# Quad_ESC_adapter.net
KiCad netlist of a schematic drawn in EAGLE
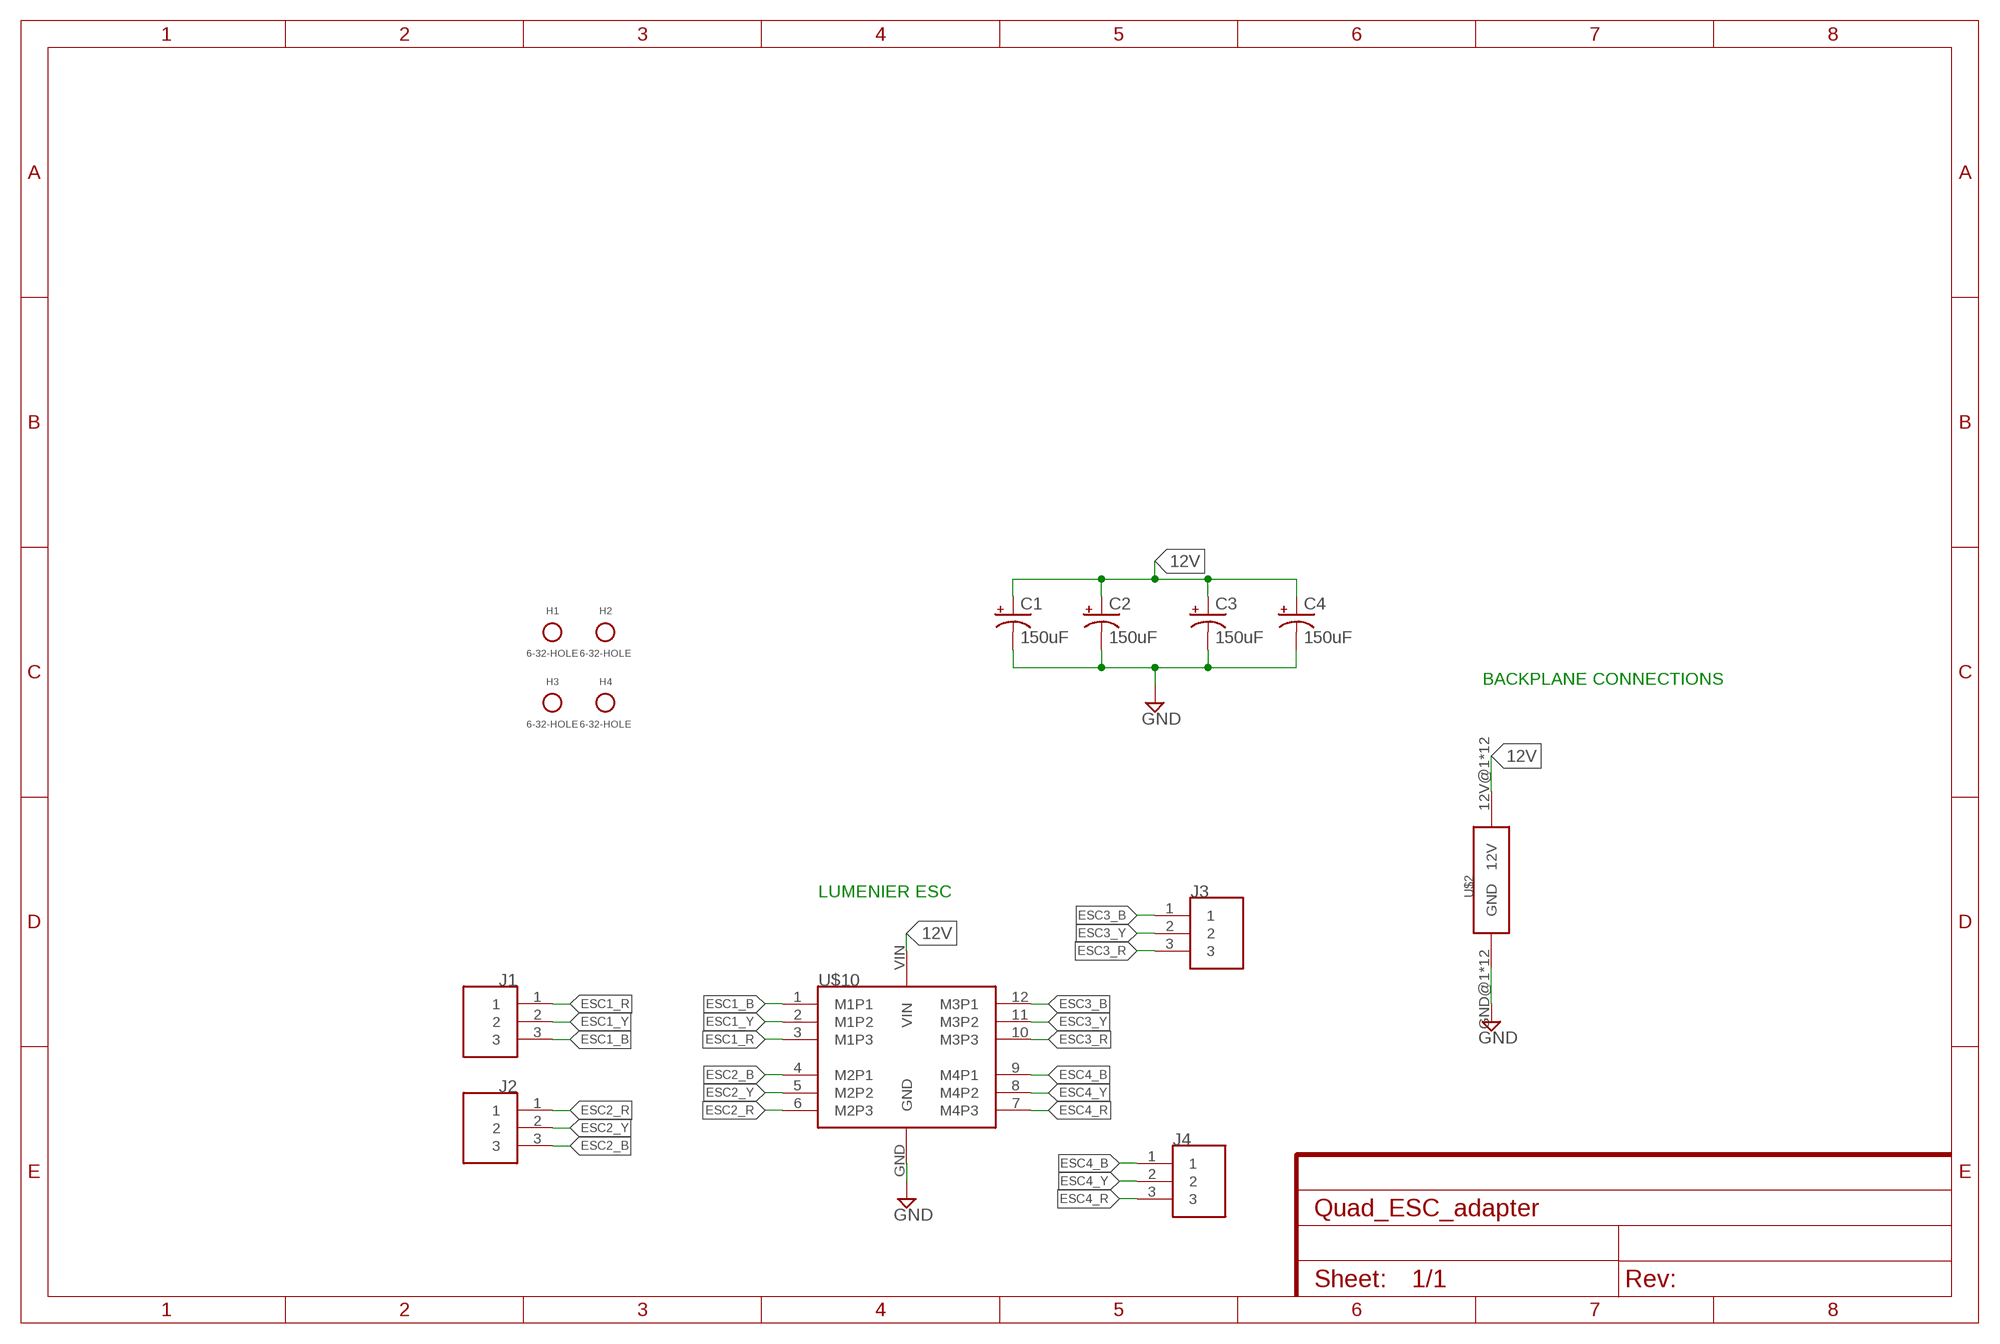
[diagram p0: schematic, sheet 1]

(export (version "E")
  (design (tool "Eeschema 10.0.6"))
  (components
    (comp (ref "C1")
      (value "150uF")
      (footprint "eagle-import:2917(7343-31-METRIC)")
      (libsource (lib "eagle-import") (part "C-TANTALUM(10UF_150UF)"))
    )
    (comp (ref "C2")
      (value "150uF")
      (footprint "eagle-import:2917(7343-31-METRIC)")
      (libsource (lib "eagle-import") (part "C-TANTALUM(10UF_150UF)"))
    )
    (comp (ref "C3")
      (value "150uF")
      (footprint "eagle-import:2917(7343-31-METRIC)")
      (libsource (lib "eagle-import") (part "C-TANTALUM(10UF_150UF)"))
    )
    (comp (ref "C4")
      (value "150uF")
      (footprint "eagle-import:2917(7343-31-METRIC)")
      (libsource (lib "eagle-import") (part "C-TANTALUM(10UF_150UF)"))
    )
    (comp (ref "H1")
      (value "6-32-HOLE")
      (footprint "eagle-import:6-32-HOLE")
      (libsource (lib "eagle-import") (part "6-32-HOLE"))
    )
    (comp (ref "H2")
      (value "6-32-HOLE")
      (footprint "eagle-import:6-32-HOLE")
      (libsource (lib "eagle-import") (part "6-32-HOLE"))
    )
    (comp (ref "H3")
      (value "6-32-HOLE")
      (footprint "eagle-import:6-32-HOLE")
      (libsource (lib "eagle-import") (part "6-32-HOLE"))
    )
    (comp (ref "H4")
      (value "6-32-HOLE")
      (footprint "eagle-import:6-32-HOLE")
      (libsource (lib "eagle-import") (part "6-32-HOLE"))
    )
    (comp (ref "J1")
      (value "284512-3")
      (footprint "eagle-import:284512-3")
      (libsource (lib "eagle-import") (part "284512-3"))
    )
    (comp (ref "J2")
      (value "284512-3")
      (footprint "eagle-import:284512-3")
      (libsource (lib "eagle-import") (part "284512-3"))
    )
    (comp (ref "J3")
      (value "284512-3")
      (footprint "eagle-import:284512-3")
      (libsource (lib "eagle-import") (part "284512-3"))
    )
    (comp (ref "J4")
      (value "284512-3")
      (footprint "eagle-import:284512-3")
      (libsource (lib "eagle-import") (part "284512-3"))
    )
    (comp (ref "U$2")
      (value "BACKPLANE_ESC_ADAPTER_PWRESC")
      (footprint "eagle-import:BACKPLANE_ESC_ADAPTER_ESC_PWR")
      (libsource (lib "eagle-import") (part "BACKPLANE_ESC_ADAPTER_PWRESC"))
    )
    (comp (ref "U$10")
      (value "LUMENIER_QUAD-NO-CUT")
      (footprint "eagle-import:LUMENIER_QUAD-NO-CUT")
      (libsource (lib "eagle-import") (part "LUMENIER_QUAD-NO-CUT"))
    )
  )
  (nets
    (net (code "1") (name "12V") (class "Default")
      (node (ref "C1") (pin "+") (pinfunction "+_+") (pintype "passive"))
      (node (ref "C2") (pin "+") (pinfunction "+_+") (pintype "passive"))
      (node (ref "C3") (pin "+") (pinfunction "+_+") (pintype "passive"))
      (node (ref "C4") (pin "+") (pinfunction "+_+") (pintype "passive"))
      (node (ref "U$10") (pin "VIN") (pinfunction "VIN_VIN") (pintype "bidirectional"))
      (node (ref "U$2") (pin "12V@1") (pinfunction "12V_12V@1") (pintype "bidirectional"))
      (node (ref "U$2") (pin "12V@10") (pinfunction "12V_12V@10") (pintype "bidirectional"))
      (node (ref "U$2") (pin "12V@11") (pinfunction "12V_12V@11") (pintype "bidirectional"))
      (node (ref "U$2") (pin "12V@12") (pinfunction "12V_12V@12") (pintype "bidirectional"))
      (node (ref "U$2") (pin "12V@2") (pinfunction "12V_12V@2") (pintype "bidirectional"))
      (node (ref "U$2") (pin "12V@3") (pinfunction "12V_12V@3") (pintype "bidirectional"))
      (node (ref "U$2") (pin "12V@4") (pinfunction "12V_12V@4") (pintype "bidirectional"))
      (node (ref "U$2") (pin "12V@5") (pinfunction "12V_12V@5") (pintype "bidirectional"))
      (node (ref "U$2") (pin "12V@6") (pinfunction "12V_12V@6") (pintype "bidirectional"))
      (node (ref "U$2") (pin "12V@7") (pinfunction "12V_12V@7") (pintype "bidirectional"))
      (node (ref "U$2") (pin "12V@8") (pinfunction "12V_12V@8") (pintype "bidirectional"))
      (node (ref "U$2") (pin "12V@9") (pinfunction "12V_12V@9") (pintype "bidirectional"))
    )
    (net (code "2") (name "ESC1_B") (class "Default")
      (node (ref "J1") (pin "3") (pinfunction "3_3") (pintype "bidirectional"))
      (node (ref "U$10") (pin "1") (pinfunction "M1P1_1") (pintype "bidirectional"))
    )
    (net (code "3") (name "ESC1_R") (class "Default")
      (node (ref "J1") (pin "1") (pinfunction "1_1") (pintype "bidirectional"))
      (node (ref "U$10") (pin "3") (pinfunction "M1P3_3") (pintype "bidirectional"))
    )
    (net (code "4") (name "ESC1_Y") (class "Default")
      (node (ref "J1") (pin "2") (pinfunction "2_2") (pintype "bidirectional"))
      (node (ref "U$10") (pin "2") (pinfunction "M1P2_2") (pintype "bidirectional"))
    )
    (net (code "5") (name "ESC2_B") (class "Default")
      (node (ref "J2") (pin "3") (pinfunction "3_3") (pintype "bidirectional"))
      (node (ref "U$10") (pin "4") (pinfunction "M2P1_4") (pintype "bidirectional"))
    )
    (net (code "6") (name "ESC2_R") (class "Default")
      (node (ref "J2") (pin "1") (pinfunction "1_1") (pintype "bidirectional"))
      (node (ref "U$10") (pin "6") (pinfunction "M2P3_6") (pintype "bidirectional"))
    )
    (net (code "7") (name "ESC2_Y") (class "Default")
      (node (ref "J2") (pin "2") (pinfunction "2_2") (pintype "bidirectional"))
      (node (ref "U$10") (pin "5") (pinfunction "M2P2_5") (pintype "bidirectional"))
    )
    (net (code "8") (name "ESC3_B") (class "Default")
      (node (ref "J3") (pin "1") (pinfunction "1_1") (pintype "bidirectional"))
      (node (ref "U$10") (pin "12") (pinfunction "M3P1_12") (pintype "bidirectional"))
    )
    (net (code "9") (name "ESC3_R") (class "Default")
      (node (ref "J3") (pin "3") (pinfunction "3_3") (pintype "bidirectional"))
      (node (ref "U$10") (pin "10") (pinfunction "M3P3_10") (pintype "bidirectional"))
    )
    (net (code "10") (name "ESC3_Y") (class "Default")
      (node (ref "J3") (pin "2") (pinfunction "2_2") (pintype "bidirectional"))
      (node (ref "U$10") (pin "11") (pinfunction "M3P2_11") (pintype "bidirectional"))
    )
    (net (code "11") (name "ESC4_B") (class "Default")
      (node (ref "J4") (pin "1") (pinfunction "1_1") (pintype "bidirectional"))
      (node (ref "U$10") (pin "9") (pinfunction "M4P1_9") (pintype "bidirectional"))
    )
    (net (code "12") (name "ESC4_R") (class "Default")
      (node (ref "J4") (pin "3") (pinfunction "3_3") (pintype "bidirectional"))
      (node (ref "U$10") (pin "7") (pinfunction "M4P3_7") (pintype "bidirectional"))
    )
    (net (code "13") (name "ESC4_Y") (class "Default")
      (node (ref "J4") (pin "2") (pinfunction "2_2") (pintype "bidirectional"))
      (node (ref "U$10") (pin "8") (pinfunction "M4P2_8") (pintype "bidirectional"))
    )
    (net (code "14") (name "GND") (class "Default")
      (node (ref "C1") (pin "-") (pinfunction "-_-") (pintype "passive"))
      (node (ref "C2") (pin "-") (pinfunction "-_-") (pintype "passive"))
      (node (ref "C3") (pin "-") (pinfunction "-_-") (pintype "passive"))
      (node (ref "C4") (pin "-") (pinfunction "-_-") (pintype "passive"))
      (node (ref "U$10") (pin "GND") (pinfunction "GND_GND") (pintype "bidirectional"))
      (node (ref "U$2") (pin "GND@1") (pinfunction "GND_GND@1") (pintype "bidirectional"))
      (node (ref "U$2") (pin "GND@10") (pinfunction "GND_GND@10") (pintype "bidirectional"))
      (node (ref "U$2") (pin "GND@11") (pinfunction "GND_GND@11") (pintype "bidirectional"))
      (node (ref "U$2") (pin "GND@12") (pinfunction "GND_GND@12") (pintype "bidirectional"))
      (node (ref "U$2") (pin "GND@2") (pinfunction "GND_GND@2") (pintype "bidirectional"))
      (node (ref "U$2") (pin "GND@3") (pinfunction "GND_GND@3") (pintype "bidirectional"))
      (node (ref "U$2") (pin "GND@4") (pinfunction "GND_GND@4") (pintype "bidirectional"))
      (node (ref "U$2") (pin "GND@5") (pinfunction "GND_GND@5") (pintype "bidirectional"))
      (node (ref "U$2") (pin "GND@6") (pinfunction "GND_GND@6") (pintype "bidirectional"))
      (node (ref "U$2") (pin "GND@7") (pinfunction "GND_GND@7") (pintype "bidirectional"))
      (node (ref "U$2") (pin "GND@8") (pinfunction "GND_GND@8") (pintype "bidirectional"))
      (node (ref "U$2") (pin "GND@9") (pinfunction "GND_GND@9") (pintype "bidirectional"))
    )
  )
)
